# BOB-001.net
KiCad netlist of a schematic drawn in EAGLE
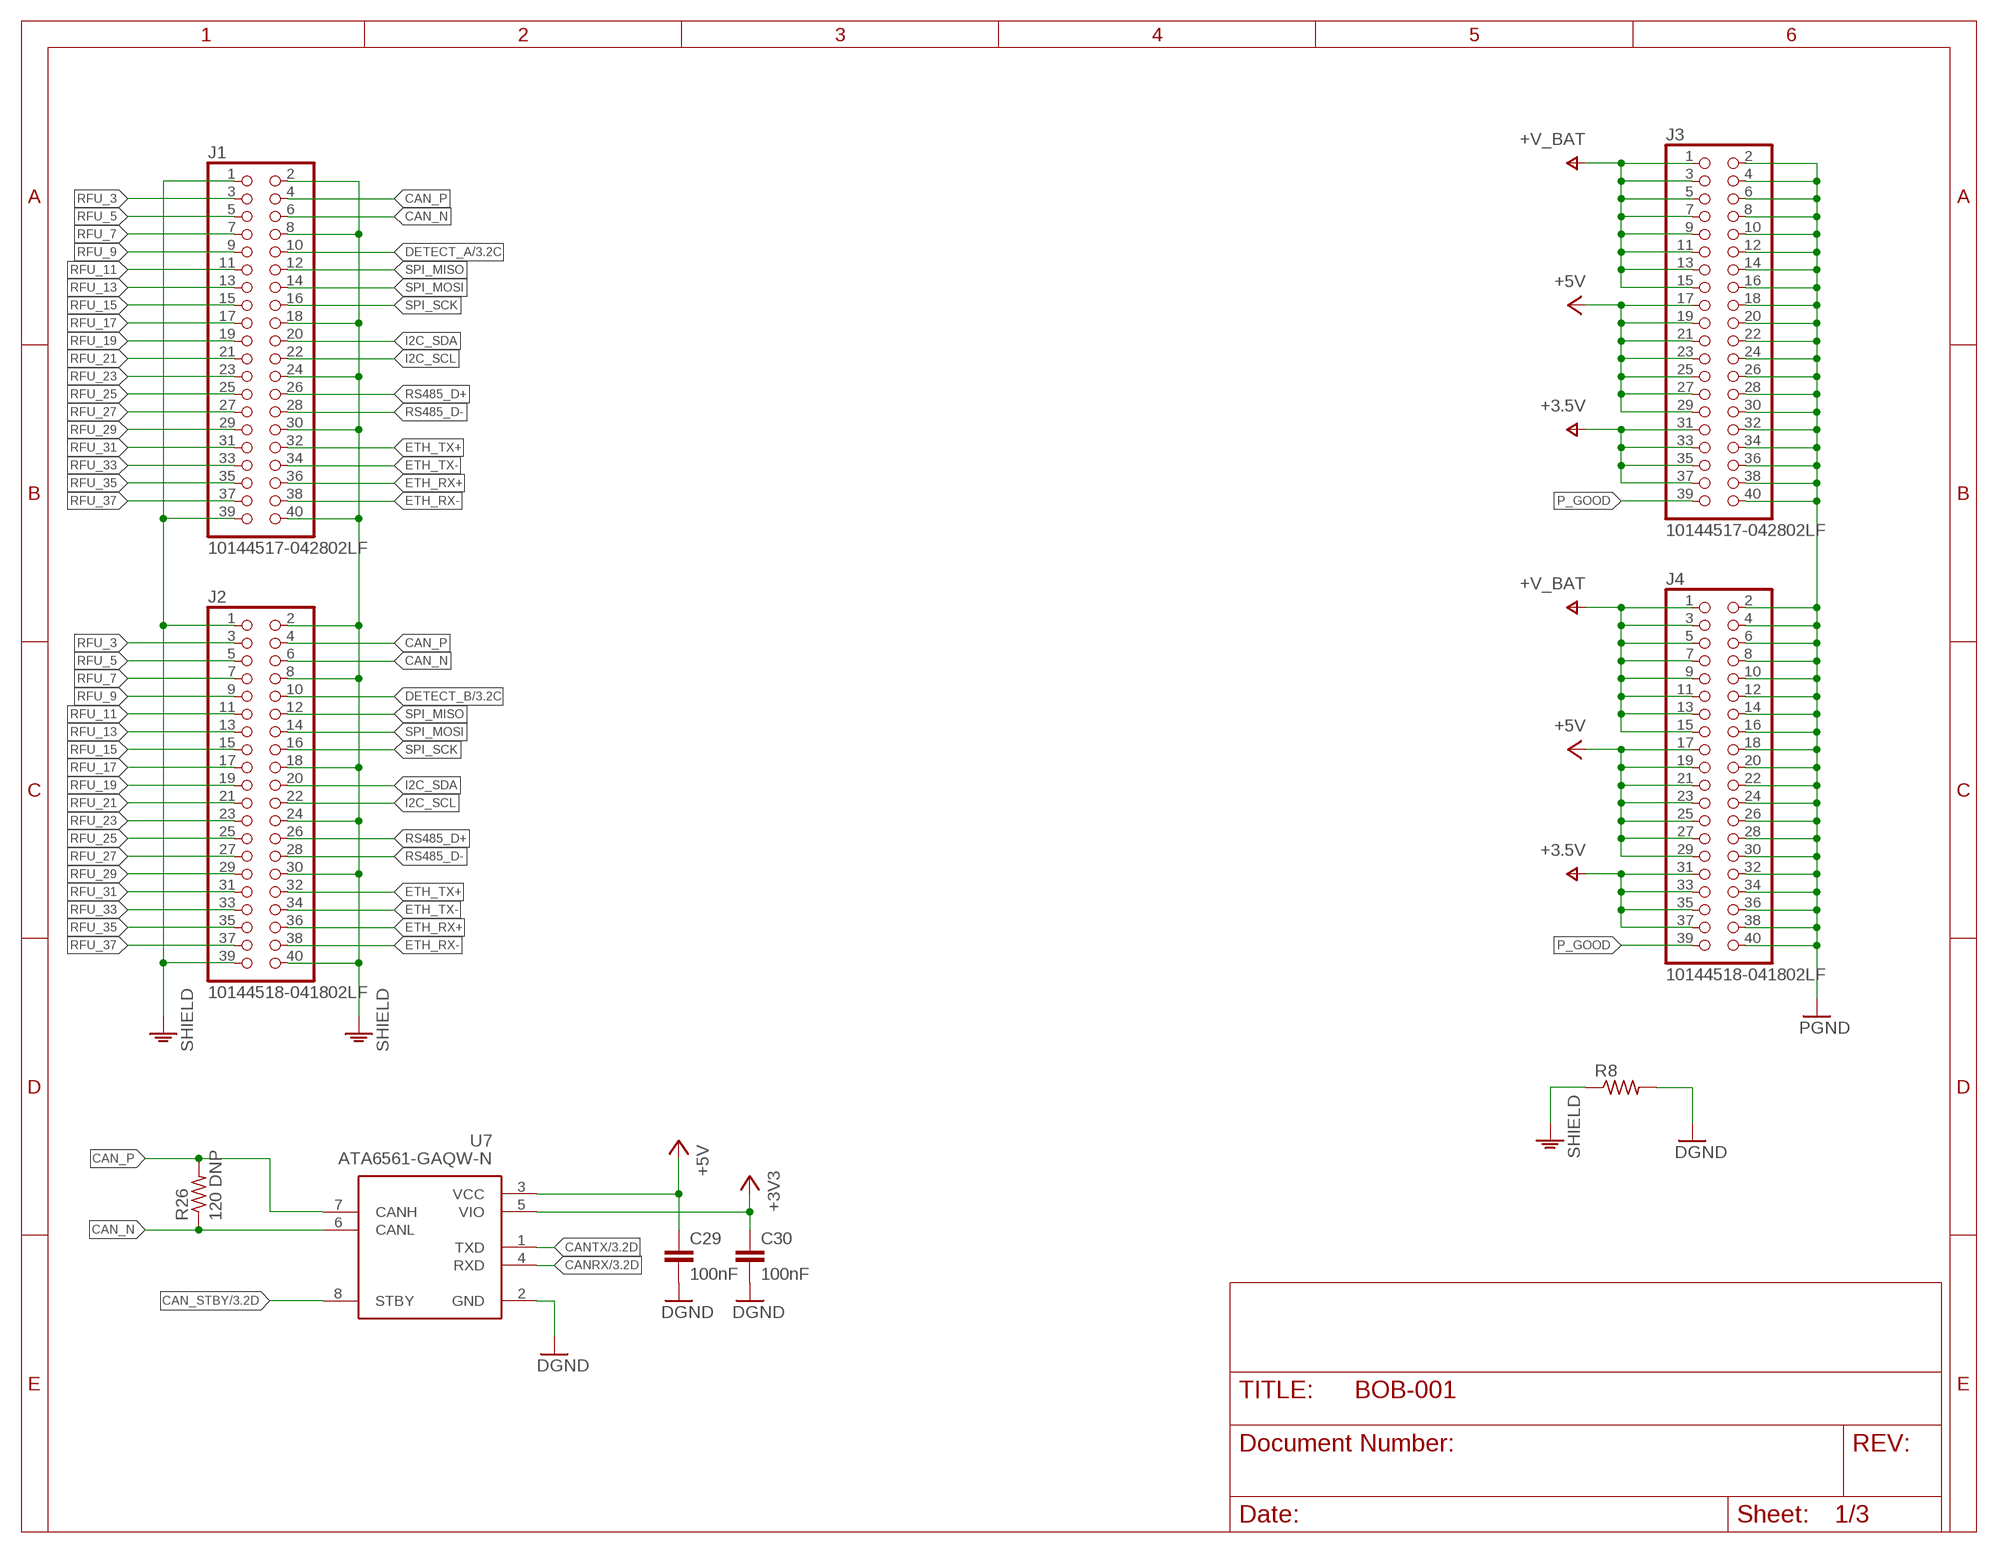
[diagram p0: schematic, sheet 1]
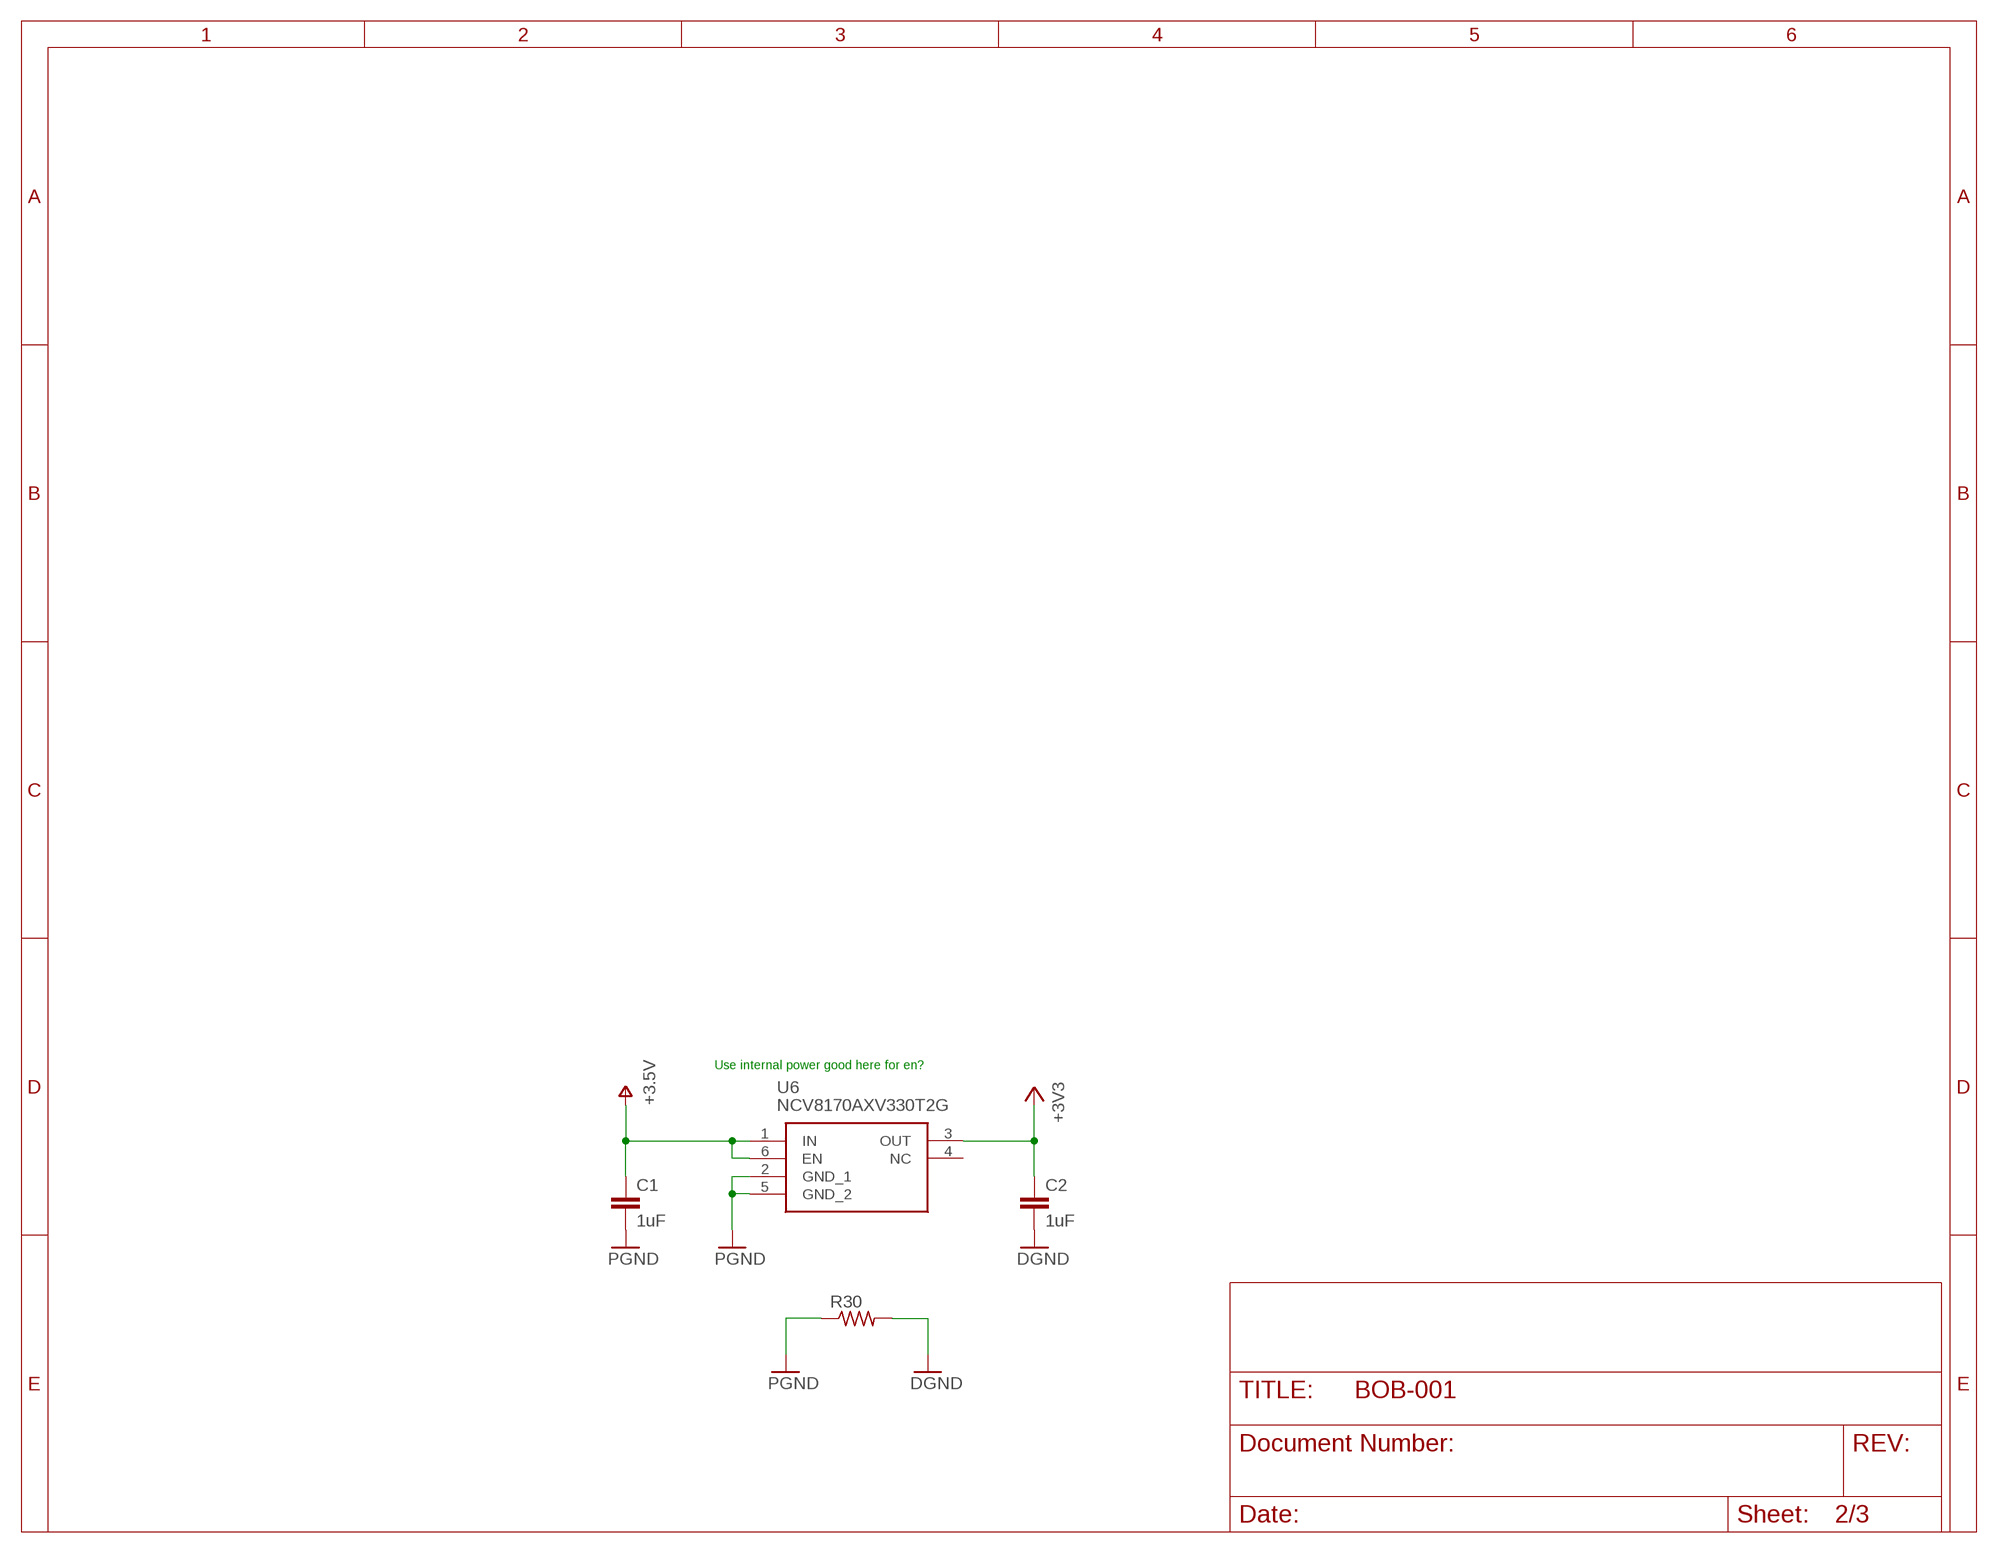
[diagram p1: schematic, sheet 2]
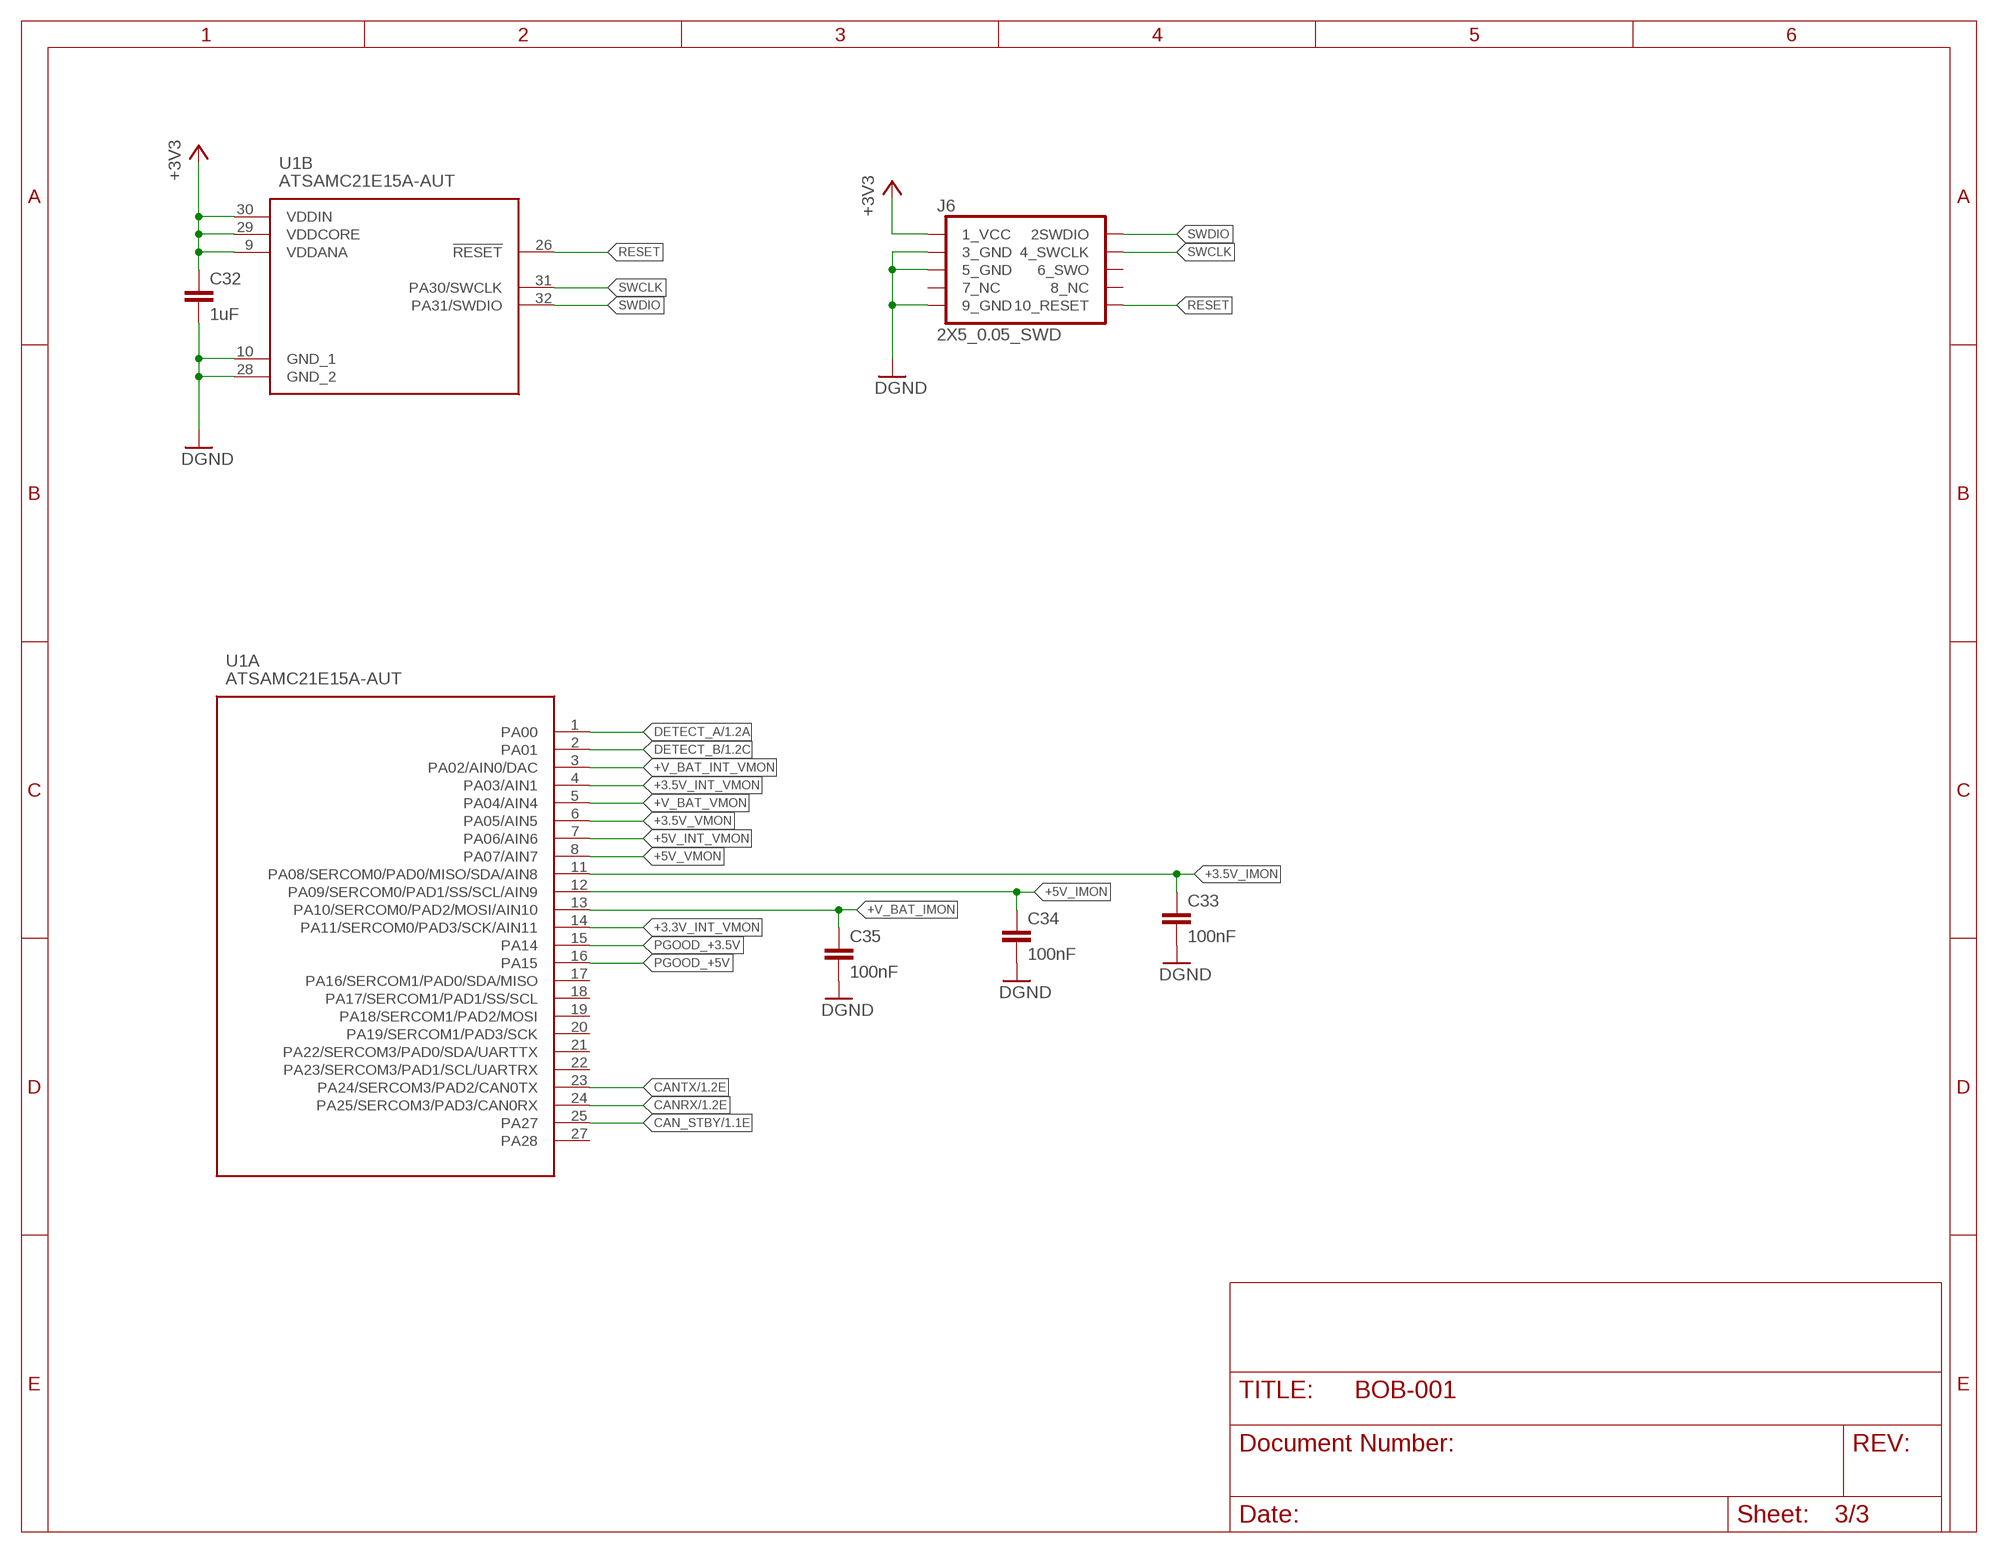
[diagram p2: schematic, sheet 3]

(export (version "E")
  (design (tool "Eeschema 10.0.6"))
  (components
    (comp (ref "C1")
      (value "1uF")
      (footprint "eagle-import:C0603")
      (libsource (lib "eagle-import") (part "C-EUC0603"))
    )
    (comp (ref "C2")
      (value "1uF")
      (footprint "eagle-import:C0603")
      (libsource (lib "eagle-import") (part "C-EUC0603"))
    )
    (comp (ref "R30")
      (value "R-US_R0402")
      (footprint "eagle-import:R0402")
      (libsource (lib "eagle-import") (part "R-US_R0402"))
    )
    (comp (ref "U6")
      (value "NCV8170AXV330T2G")
      (footprint "eagle-import:SOTFL50P160X60-6N")
      (fields (field (name "MOUSER_PART_NUMBER") "863-NCV8170AXV330T2G"))
      (libsource (lib "eagle-import") (part "NCV8170AXV330T2G"))
    )
    (comp (ref "C29")
      (value "100nF")
      (footprint "eagle-import:C0402")
      (libsource (lib "eagle-import") (part "C-EUC0402"))
    )
    (comp (ref "C30")
      (value "100nF")
      (footprint "eagle-import:C0402")
      (libsource (lib "eagle-import") (part "C-EUC0402"))
    )
    (comp (ref "J1")
      (value "10144517-042802LF")
      (footprint "eagle-import:10144517-042802LF")
      (libsource (lib "eagle-import") (part "10144517-042802LF"))
    )
    (comp (ref "J2")
      (value "10144518-041802LF")
      (footprint "eagle-import:10144518-041802LF")
      (libsource (lib "eagle-import") (part "10144518-041802LF"))
    )
    (comp (ref "J3")
      (value "10144517-042802LF")
      (footprint "eagle-import:10144517-042802LF")
      (libsource (lib "eagle-import") (part "10144517-042802LF"))
    )
    (comp (ref "J4")
      (value "10144518-041802LF")
      (footprint "eagle-import:10144518-041802LF")
      (libsource (lib "eagle-import") (part "10144518-041802LF"))
    )
    (comp (ref "R8")
      (value "R-US_R0402")
      (footprint "eagle-import:R0402")
      (libsource (lib "eagle-import") (part "R-US_R0402"))
    )
    (comp (ref "R26")
      (value "120 DNP")
      (footprint "eagle-import:R0402")
      (libsource (lib "eagle-import") (part "R-US_R0402"))
    )
    (comp (ref "U7")
      (value "ATA6561-GAQW-N")
      (footprint "eagle-import:SOIC127P600X175-8N")
      (fields (field (name "MOUSER_PART_NUMBER") "579-ATA6561-GAQW-N"))
      (libsource (lib "eagle-import") (part "ATA6561-GAQW-N"))
    )
    (comp (ref "C32")
      (value "1uF")
      (footprint "eagle-import:C0805")
      (libsource (lib "eagle-import") (part "C-EUC0805"))
    )
    (comp (ref "C33")
      (value "100nF")
      (footprint "eagle-import:C0402")
      (libsource (lib "eagle-import") (part "C-EUC0402"))
    )
    (comp (ref "C34")
      (value "100nF")
      (footprint "eagle-import:C0402")
      (libsource (lib "eagle-import") (part "C-EUC0402"))
    )
    (comp (ref "C35")
      (value "100nF")
      (footprint "eagle-import:C0402")
      (libsource (lib "eagle-import") (part "C-EUC0402"))
    )
    (comp (ref "J6")
      (value "2X5_0.05_SWD")
      (footprint "eagle-import:2X5_RIGHT")
      (libsource (lib "eagle-import") (part "2X5_0.05_SWD"))
    )
    (comp (ref "U1")
      (value "ATSAMC21E15A-AUT")
      (footprint "eagle-import:QFP80P900X900X120-32N")
      (libsource (lib "eagle-import") (part "ATSAMC21E15A-AUT"))
    )
  )
  (nets
    (net (code "1") (name "+3.3V_INT_VMON") (class "Default")
      (node (ref "U1") (pin "14") (pinfunction "PA11/SERCOM0/PAD3/SCK/AIN11_14") (pintype "bidirectional"))
    )
    (net (code "2") (name "+3.5V") (class "Default")
      (node (ref "C1") (pin "1") (pinfunction "1_1") (pintype "passive"))
      (node (ref "J3") (pin "31") (pinfunction "31_31") (pintype "passive"))
      (node (ref "J3") (pin "33") (pinfunction "33_33") (pintype "passive"))
      (node (ref "J3") (pin "35") (pinfunction "35_35") (pintype "passive"))
      (node (ref "J3") (pin "37") (pinfunction "37_37") (pintype "passive"))
      (node (ref "J4") (pin "31") (pinfunction "31_31") (pintype "passive"))
      (node (ref "J4") (pin "33") (pinfunction "33_33") (pintype "passive"))
      (node (ref "J4") (pin "35") (pinfunction "35_35") (pintype "passive"))
      (node (ref "J4") (pin "37") (pinfunction "37_37") (pintype "passive"))
      (node (ref "U6") (pin "1") (pinfunction "IN_1") (pintype "bidirectional"))
      (node (ref "U6") (pin "6") (pinfunction "EN_6") (pintype "bidirectional"))
    )
    (net (code "3") (name "+3.5V_IMON") (class "Default")
      (node (ref "C33") (pin "1") (pinfunction "1_1") (pintype "passive"))
      (node (ref "U1") (pin "11") (pinfunction "PA08/SERCOM0/PAD0/MISO/SDA/AIN8_11") (pintype "bidirectional"))
    )
    (net (code "4") (name "+3.5V_INT_VMON") (class "Default")
      (node (ref "U1") (pin "4") (pinfunction "PA03/AIN1_4") (pintype "bidirectional"))
    )
    (net (code "5") (name "+3.5V_VMON") (class "Default")
      (node (ref "U1") (pin "6") (pinfunction "PA05/AIN5_6") (pintype "bidirectional"))
    )
    (net (code "6") (name "+3V3") (class "Default")
      (node (ref "C2") (pin "1") (pinfunction "1_1") (pintype "passive"))
      (node (ref "C30") (pin "1") (pinfunction "1_1") (pintype "passive"))
      (node (ref "C32") (pin "1") (pinfunction "1_1") (pintype "passive"))
      (node (ref "J6") (pin "1") (pinfunction "1_VCC_1") (pintype "passive"))
      (node (ref "U1") (pin "29") (pinfunction "VDDCORE_29") (pintype "power_in"))
      (node (ref "U1") (pin "30") (pinfunction "VDDIN_30") (pintype "power_in"))
      (node (ref "U1") (pin "9") (pinfunction "VDDANA_9") (pintype "power_in"))
      (node (ref "U6") (pin "3") (pinfunction "OUT_3") (pintype "bidirectional"))
      (node (ref "U7") (pin "5") (pinfunction "VIO_5") (pintype "bidirectional"))
    )
    (net (code "7") (name "+5V") (class "Default")
      (node (ref "C29") (pin "1") (pinfunction "1_1") (pintype "passive"))
      (node (ref "J3") (pin "17") (pinfunction "17_17") (pintype "passive"))
      (node (ref "J3") (pin "19") (pinfunction "19_19") (pintype "passive"))
      (node (ref "J3") (pin "21") (pinfunction "21_21") (pintype "passive"))
      (node (ref "J3") (pin "23") (pinfunction "23_23") (pintype "passive"))
      (node (ref "J3") (pin "25") (pinfunction "25_25") (pintype "passive"))
      (node (ref "J3") (pin "27") (pinfunction "27_27") (pintype "passive"))
      (node (ref "J3") (pin "29") (pinfunction "29_29") (pintype "passive"))
      (node (ref "J4") (pin "17") (pinfunction "17_17") (pintype "passive"))
      (node (ref "J4") (pin "19") (pinfunction "19_19") (pintype "passive"))
      (node (ref "J4") (pin "21") (pinfunction "21_21") (pintype "passive"))
      (node (ref "J4") (pin "23") (pinfunction "23_23") (pintype "passive"))
      (node (ref "J4") (pin "25") (pinfunction "25_25") (pintype "passive"))
      (node (ref "J4") (pin "27") (pinfunction "27_27") (pintype "passive"))
      (node (ref "J4") (pin "29") (pinfunction "29_29") (pintype "passive"))
      (node (ref "U7") (pin "3") (pinfunction "VCC_3") (pintype "bidirectional"))
    )
    (net (code "8") (name "+5V_IMON") (class "Default")
      (node (ref "C34") (pin "1") (pinfunction "1_1") (pintype "passive"))
      (node (ref "U1") (pin "12") (pinfunction "PA09/SERCOM0/PAD1/SS/SCL/AIN9_12") (pintype "bidirectional"))
    )
    (net (code "9") (name "+5V_INT_VMON") (class "Default")
      (node (ref "U1") (pin "7") (pinfunction "PA06/AIN6_7") (pintype "bidirectional"))
    )
    (net (code "10") (name "+5V_VMON") (class "Default")
      (node (ref "U1") (pin "8") (pinfunction "PA07/AIN7_8") (pintype "bidirectional"))
    )
    (net (code "11") (name "+V_BAT") (class "Default")
      (node (ref "J3") (pin "1") (pinfunction "1_1") (pintype "passive"))
      (node (ref "J3") (pin "11") (pinfunction "11_11") (pintype "passive"))
      (node (ref "J3") (pin "13") (pinfunction "13_13") (pintype "passive"))
      (node (ref "J3") (pin "15") (pinfunction "15_15") (pintype "passive"))
      (node (ref "J3") (pin "3") (pinfunction "3_3") (pintype "passive"))
      (node (ref "J3") (pin "5") (pinfunction "5_5") (pintype "passive"))
      (node (ref "J3") (pin "7") (pinfunction "7_7") (pintype "passive"))
      (node (ref "J3") (pin "9") (pinfunction "9_9") (pintype "passive"))
      (node (ref "J4") (pin "1") (pinfunction "1_1") (pintype "passive"))
      (node (ref "J4") (pin "11") (pinfunction "11_11") (pintype "passive"))
      (node (ref "J4") (pin "13") (pinfunction "13_13") (pintype "passive"))
      (node (ref "J4") (pin "15") (pinfunction "15_15") (pintype "passive"))
      (node (ref "J4") (pin "3") (pinfunction "3_3") (pintype "passive"))
      (node (ref "J4") (pin "5") (pinfunction "5_5") (pintype "passive"))
      (node (ref "J4") (pin "7") (pinfunction "7_7") (pintype "passive"))
      (node (ref "J4") (pin "9") (pinfunction "9_9") (pintype "passive"))
    )
    (net (code "12") (name "+V_BAT_IMON") (class "Default")
      (node (ref "C35") (pin "1") (pinfunction "1_1") (pintype "passive"))
      (node (ref "U1") (pin "13") (pinfunction "PA10/SERCOM0/PAD2/MOSI/AIN10_13") (pintype "bidirectional"))
    )
    (net (code "13") (name "+V_BAT_INT_VMON") (class "Default")
      (node (ref "U1") (pin "3") (pinfunction "PA02/AIN0/DAC_3") (pintype "bidirectional"))
    )
    (net (code "14") (name "+V_BAT_VMON") (class "Default")
      (node (ref "U1") (pin "5") (pinfunction "PA04/AIN4_5") (pintype "bidirectional"))
    )
    (net (code "15") (name "CANRX") (class "Default")
      (node (ref "U1") (pin "24") (pinfunction "PA25/SERCOM3/PAD3/CAN0RX_24") (pintype "bidirectional"))
      (node (ref "U7") (pin "4") (pinfunction "RXD_4") (pintype "bidirectional"))
    )
    (net (code "16") (name "CANTX") (class "Default")
      (node (ref "U1") (pin "23") (pinfunction "PA24/SERCOM3/PAD2/CAN0TX_23") (pintype "bidirectional"))
      (node (ref "U7") (pin "1") (pinfunction "TXD_1") (pintype "bidirectional"))
    )
    (net (code "17") (name "CAN_N") (class "Default")
      (node (ref "J1") (pin "6") (pinfunction "6_6") (pintype "passive"))
      (node (ref "J2") (pin "6") (pinfunction "6_6") (pintype "passive"))
      (node (ref "R26") (pin "1") (pinfunction "1_1") (pintype "passive"))
      (node (ref "U7") (pin "6") (pinfunction "CANL_6") (pintype "bidirectional"))
    )
    (net (code "18") (name "CAN_P") (class "Default")
      (node (ref "J1") (pin "4") (pinfunction "4_4") (pintype "passive"))
      (node (ref "J2") (pin "4") (pinfunction "4_4") (pintype "passive"))
      (node (ref "R26") (pin "2") (pinfunction "2_2") (pintype "passive"))
      (node (ref "U7") (pin "7") (pinfunction "CANH_7") (pintype "bidirectional"))
    )
    (net (code "19") (name "CAN_STBY") (class "Default")
      (node (ref "U1") (pin "25") (pinfunction "PA27_25") (pintype "bidirectional"))
      (node (ref "U7") (pin "8") (pinfunction "STBY_8") (pintype "bidirectional"))
    )
    (net (code "20") (name "DETECT_A") (class "Default")
      (node (ref "J1") (pin "10") (pinfunction "10_10") (pintype "passive"))
      (node (ref "U1") (pin "1") (pinfunction "PA00_1") (pintype "bidirectional"))
    )
    (net (code "21") (name "DETECT_B") (class "Default")
      (node (ref "J2") (pin "10") (pinfunction "10_10") (pintype "passive"))
      (node (ref "U1") (pin "2") (pinfunction "PA01_2") (pintype "bidirectional"))
    )
    (net (code "22") (name "DGND") (class "Default")
      (node (ref "C2") (pin "2") (pinfunction "2_2") (pintype "passive"))
      (node (ref "C29") (pin "2") (pinfunction "2_2") (pintype "passive"))
      (node (ref "C30") (pin "2") (pinfunction "2_2") (pintype "passive"))
      (node (ref "C32") (pin "2") (pinfunction "2_2") (pintype "passive"))
      (node (ref "C33") (pin "2") (pinfunction "2_2") (pintype "passive"))
      (node (ref "C34") (pin "2") (pinfunction "2_2") (pintype "passive"))
      (node (ref "C35") (pin "2") (pinfunction "2_2") (pintype "passive"))
      (node (ref "J6") (pin "3") (pinfunction "3_GND_3") (pintype "passive"))
      (node (ref "J6") (pin "5") (pinfunction "5_GND_5") (pintype "passive"))
      (node (ref "J6") (pin "9") (pinfunction "9_GND_9") (pintype "passive"))
      (node (ref "R30") (pin "2") (pinfunction "2_2") (pintype "passive"))
      (node (ref "R8") (pin "2") (pinfunction "2_2") (pintype "passive"))
      (node (ref "U1") (pin "10") (pinfunction "GND_1_10") (pintype "power_in"))
      (node (ref "U1") (pin "28") (pinfunction "GND_2_28") (pintype "power_in"))
      (node (ref "U7") (pin "2") (pinfunction "GND_2") (pintype "bidirectional"))
    )
    (net (code "23") (name "ETH_RX+") (class "Default")
      (node (ref "J1") (pin "36") (pinfunction "36_36") (pintype "passive"))
      (node (ref "J2") (pin "36") (pinfunction "36_36") (pintype "passive"))
    )
    (net (code "24") (name "ETH_RX-") (class "Default")
      (node (ref "J1") (pin "38") (pinfunction "38_38") (pintype "passive"))
      (node (ref "J2") (pin "38") (pinfunction "38_38") (pintype "passive"))
    )
    (net (code "25") (name "ETH_TX+") (class "Default")
      (node (ref "J1") (pin "32") (pinfunction "32_32") (pintype "passive"))
      (node (ref "J2") (pin "32") (pinfunction "32_32") (pintype "passive"))
    )
    (net (code "26") (name "ETH_TX-") (class "Default")
      (node (ref "J1") (pin "34") (pinfunction "34_34") (pintype "passive"))
      (node (ref "J2") (pin "34") (pinfunction "34_34") (pintype "passive"))
    )
    (net (code "27") (name "I2C_SCL") (class "Default")
      (node (ref "J1") (pin "22") (pinfunction "22_22") (pintype "passive"))
      (node (ref "J2") (pin "22") (pinfunction "22_22") (pintype "passive"))
    )
    (net (code "28") (name "I2C_SDA") (class "Default")
      (node (ref "J1") (pin "20") (pinfunction "20_20") (pintype "passive"))
      (node (ref "J2") (pin "20") (pinfunction "20_20") (pintype "passive"))
    )
    (net (code "29") (name "PGND") (class "Default")
      (node (ref "C1") (pin "2") (pinfunction "2_2") (pintype "passive"))
      (node (ref "J3") (pin "10") (pinfunction "10_10") (pintype "passive"))
      (node (ref "J3") (pin "12") (pinfunction "12_12") (pintype "passive"))
      (node (ref "J3") (pin "14") (pinfunction "14_14") (pintype "passive"))
      (node (ref "J3") (pin "16") (pinfunction "16_16") (pintype "passive"))
      (node (ref "J3") (pin "18") (pinfunction "18_18") (pintype "passive"))
      (node (ref "J3") (pin "2") (pinfunction "2_2") (pintype "passive"))
      (node (ref "J3") (pin "20") (pinfunction "20_20") (pintype "passive"))
      (node (ref "J3") (pin "22") (pinfunction "22_22") (pintype "passive"))
      (node (ref "J3") (pin "24") (pinfunction "24_24") (pintype "passive"))
      (node (ref "J3") (pin "26") (pinfunction "26_26") (pintype "passive"))
      (node (ref "J3") (pin "28") (pinfunction "28_28") (pintype "passive"))
      (node (ref "J3") (pin "30") (pinfunction "30_30") (pintype "passive"))
      (node (ref "J3") (pin "32") (pinfunction "32_32") (pintype "passive"))
      (node (ref "J3") (pin "34") (pinfunction "34_34") (pintype "passive"))
      (node (ref "J3") (pin "36") (pinfunction "36_36") (pintype "passive"))
      (node (ref "J3") (pin "38") (pinfunction "38_38") (pintype "passive"))
      (node (ref "J3") (pin "4") (pinfunction "4_4") (pintype "passive"))
      (node (ref "J3") (pin "40") (pinfunction "40_40") (pintype "passive"))
      (node (ref "J3") (pin "6") (pinfunction "6_6") (pintype "passive"))
      (node (ref "J3") (pin "8") (pinfunction "8_8") (pintype "passive"))
      (node (ref "J4") (pin "10") (pinfunction "10_10") (pintype "passive"))
      (node (ref "J4") (pin "12") (pinfunction "12_12") (pintype "passive"))
      (node (ref "J4") (pin "14") (pinfunction "14_14") (pintype "passive"))
      (node (ref "J4") (pin "16") (pinfunction "16_16") (pintype "passive"))
      (node (ref "J4") (pin "18") (pinfunction "18_18") (pintype "passive"))
      (node (ref "J4") (pin "2") (pinfunction "2_2") (pintype "passive"))
      (node (ref "J4") (pin "20") (pinfunction "20_20") (pintype "passive"))
      (node (ref "J4") (pin "22") (pinfunction "22_22") (pintype "passive"))
      (node (ref "J4") (pin "24") (pinfunction "24_24") (pintype "passive"))
      (node (ref "J4") (pin "26") (pinfunction "26_26") (pintype "passive"))
      (node (ref "J4") (pin "28") (pinfunction "28_28") (pintype "passive"))
      (node (ref "J4") (pin "30") (pinfunction "30_30") (pintype "passive"))
      (node (ref "J4") (pin "32") (pinfunction "32_32") (pintype "passive"))
      (node (ref "J4") (pin "34") (pinfunction "34_34") (pintype "passive"))
      (node (ref "J4") (pin "36") (pinfunction "36_36") (pintype "passive"))
      (node (ref "J4") (pin "38") (pinfunction "38_38") (pintype "passive"))
      (node (ref "J4") (pin "4") (pinfunction "4_4") (pintype "passive"))
      (node (ref "J4") (pin "40") (pinfunction "40_40") (pintype "passive"))
      (node (ref "J4") (pin "6") (pinfunction "6_6") (pintype "passive"))
      (node (ref "J4") (pin "8") (pinfunction "8_8") (pintype "passive"))
      (node (ref "R30") (pin "1") (pinfunction "1_1") (pintype "passive"))
      (node (ref "U6") (pin "2") (pinfunction "GND_1_2") (pintype "bidirectional"))
      (node (ref "U6") (pin "5") (pinfunction "GND_2_5") (pintype "bidirectional"))
    )
    (net (code "30") (name "PGOOD_+3.5V") (class "Default")
      (node (ref "U1") (pin "15") (pinfunction "PA14_15") (pintype "bidirectional"))
    )
    (net (code "31") (name "PGOOD_+5V") (class "Default")
      (node (ref "U1") (pin "16") (pinfunction "PA15_16") (pintype "bidirectional"))
    )
    (net (code "32") (name "P_GOOD") (class "Default")
      (node (ref "J3") (pin "39") (pinfunction "39_39") (pintype "passive"))
      (node (ref "J4") (pin "39") (pinfunction "39_39") (pintype "passive"))
    )
    (net (code "33") (name "RESET") (class "Default")
      (node (ref "J6") (pin "10") (pinfunction "10_RESET_10") (pintype "passive"))
      (node (ref "U1") (pin "26") (pinfunction "~{RESET}_26") (pintype "input"))
    )
    (net (code "34") (name "RFU_3") (class "Default")
      (node (ref "J1") (pin "3") (pinfunction "3_3") (pintype "passive"))
      (node (ref "J2") (pin "3") (pinfunction "3_3") (pintype "passive"))
    )
    (net (code "35") (name "RFU_5") (class "Default")
      (node (ref "J1") (pin "5") (pinfunction "5_5") (pintype "passive"))
      (node (ref "J2") (pin "5") (pinfunction "5_5") (pintype "passive"))
    )
    (net (code "36") (name "RFU_7") (class "Default")
      (node (ref "J1") (pin "7") (pinfunction "7_7") (pintype "passive"))
      (node (ref "J2") (pin "7") (pinfunction "7_7") (pintype "passive"))
    )
    (net (code "37") (name "RFU_9") (class "Default")
      (node (ref "J1") (pin "9") (pinfunction "9_9") (pintype "passive"))
      (node (ref "J2") (pin "9") (pinfunction "9_9") (pintype "passive"))
    )
    (net (code "38") (name "RFU_11") (class "Default")
      (node (ref "J1") (pin "11") (pinfunction "11_11") (pintype "passive"))
      (node (ref "J2") (pin "11") (pinfunction "11_11") (pintype "passive"))
    )
    (net (code "39") (name "RFU_13") (class "Default")
      (node (ref "J1") (pin "13") (pinfunction "13_13") (pintype "passive"))
      (node (ref "J2") (pin "13") (pinfunction "13_13") (pintype "passive"))
    )
    (net (code "40") (name "RFU_15") (class "Default")
      (node (ref "J1") (pin "15") (pinfunction "15_15") (pintype "passive"))
      (node (ref "J2") (pin "15") (pinfunction "15_15") (pintype "passive"))
    )
    (net (code "41") (name "RFU_17") (class "Default")
      (node (ref "J1") (pin "17") (pinfunction "17_17") (pintype "passive"))
      (node (ref "J2") (pin "17") (pinfunction "17_17") (pintype "passive"))
    )
    (net (code "42") (name "RFU_19") (class "Default")
      (node (ref "J1") (pin "19") (pinfunction "19_19") (pintype "passive"))
      (node (ref "J2") (pin "19") (pinfunction "19_19") (pintype "passive"))
    )
    (net (code "43") (name "RFU_21") (class "Default")
      (node (ref "J1") (pin "21") (pinfunction "21_21") (pintype "passive"))
      (node (ref "J2") (pin "21") (pinfunction "21_21") (pintype "passive"))
    )
    (net (code "44") (name "RFU_23") (class "Default")
      (node (ref "J1") (pin "23") (pinfunction "23_23") (pintype "passive"))
      (node (ref "J2") (pin "23") (pinfunction "23_23") (pintype "passive"))
    )
    (net (code "45") (name "RFU_25") (class "Default")
      (node (ref "J1") (pin "25") (pinfunction "25_25") (pintype "passive"))
      (node (ref "J2") (pin "25") (pinfunction "25_25") (pintype "passive"))
    )
    (net (code "46") (name "RFU_27") (class "Default")
      (node (ref "J1") (pin "27") (pinfunction "27_27") (pintype "passive"))
      (node (ref "J2") (pin "27") (pinfunction "27_27") (pintype "passive"))
    )
    (net (code "47") (name "RFU_29") (class "Default")
      (node (ref "J1") (pin "29") (pinfunction "29_29") (pintype "passive"))
      (node (ref "J2") (pin "29") (pinfunction "29_29") (pintype "passive"))
    )
    (net (code "48") (name "RFU_31") (class "Default")
      (node (ref "J1") (pin "31") (pinfunction "31_31") (pintype "passive"))
      (node (ref "J2") (pin "31") (pinfunction "31_31") (pintype "passive"))
    )
    (net (code "49") (name "RFU_33") (class "Default")
      (node (ref "J1") (pin "33") (pinfunction "33_33") (pintype "passive"))
      (node (ref "J2") (pin "33") (pinfunction "33_33") (pintype "passive"))
    )
    (net (code "50") (name "RFU_35") (class "Default")
      (node (ref "J1") (pin "35") (pinfunction "35_35") (pintype "passive"))
      (node (ref "J2") (pin "35") (pinfunction "35_35") (pintype "passive"))
    )
    (net (code "51") (name "RFU_37") (class "Default")
      (node (ref "J1") (pin "37") (pinfunction "37_37") (pintype "passive"))
      (node (ref "J2") (pin "37") (pinfunction "37_37") (pintype "passive"))
    )
    (net (code "52") (name "RS485_D+") (class "Default")
      (node (ref "J1") (pin "26") (pinfunction "26_26") (pintype "passive"))
      (node (ref "J2") (pin "26") (pinfunction "26_26") (pintype "passive"))
    )
    (net (code "53") (name "RS485_D-") (class "Default")
      (node (ref "J1") (pin "28") (pinfunction "28_28") (pintype "passive"))
      (node (ref "J2") (pin "28") (pinfunction "28_28") (pintype "passive"))
    )
    (net (code "54") (name "SHIELD") (class "Default")
      (node (ref "J1") (pin "1") (pinfunction "1_1") (pintype "passive"))
      (node (ref "J1") (pin "18") (pinfunction "18_18") (pintype "passive"))
      (node (ref "J1") (pin "2") (pinfunction "2_2") (pintype "passive"))
      (node (ref "J1") (pin "24") (pinfunction "24_24") (pintype "passive"))
      (node (ref "J1") (pin "30") (pinfunction "30_30") (pintype "passive"))
      (node (ref "J1") (pin "39") (pinfunction "39_39") (pintype "passive"))
      (node (ref "J1") (pin "40") (pinfunction "40_40") (pintype "passive"))
      (node (ref "J1") (pin "8") (pinfunction "8_8") (pintype "passive"))
      (node (ref "J2") (pin "1") (pinfunction "1_1") (pintype "passive"))
      (node (ref "J2") (pin "18") (pinfunction "18_18") (pintype "passive"))
      (node (ref "J2") (pin "2") (pinfunction "2_2") (pintype "passive"))
      (node (ref "J2") (pin "24") (pinfunction "24_24") (pintype "passive"))
      (node (ref "J2") (pin "30") (pinfunction "30_30") (pintype "passive"))
      (node (ref "J2") (pin "39") (pinfunction "39_39") (pintype "passive"))
      (node (ref "J2") (pin "40") (pinfunction "40_40") (pintype "passive"))
      (node (ref "J2") (pin "8") (pinfunction "8_8") (pintype "passive"))
      (node (ref "R8") (pin "1") (pinfunction "1_1") (pintype "passive"))
    )
    (net (code "55") (name "SPI_MISO") (class "Default")
      (node (ref "J1") (pin "12") (pinfunction "12_12") (pintype "passive"))
      (node (ref "J2") (pin "12") (pinfunction "12_12") (pintype "passive"))
    )
    (net (code "56") (name "SPI_MOSI") (class "Default")
      (node (ref "J1") (pin "14") (pinfunction "14_14") (pintype "passive"))
      (node (ref "J2") (pin "14") (pinfunction "14_14") (pintype "passive"))
    )
    (net (code "57") (name "SPI_SCK") (class "Default")
      (node (ref "J1") (pin "16") (pinfunction "16_16") (pintype "passive"))
      (node (ref "J2") (pin "16") (pinfunction "16_16") (pintype "passive"))
    )
    (net (code "58") (name "SWCLK") (class "Default")
      (node (ref "J6") (pin "4") (pinfunction "4_SWCLK_4") (pintype "passive"))
      (node (ref "U1") (pin "31") (pinfunction "PA30/SWCLK_31") (pintype "bidirectional"))
    )
    (net (code "59") (name "SWDIO") (class "Default")
      (node (ref "J6") (pin "2") (pinfunction "2SWDIO_2") (pintype "passive"))
      (node (ref "U1") (pin "32") (pinfunction "PA31/SWDIO_32") (pintype "bidirectional"))
    )
    (net (code "60") (name "unconnected-(J6-6_SWO-Pad6)") (class "Default")
      (node (ref "J6") (pin "6") (pinfunction "6_SWO_6") (pintype "passive"))
    )
    (net (code "61") (name "unconnected-(J6-7_NC-Pad7)") (class "Default")
      (node (ref "J6") (pin "7") (pinfunction "7_NC_7") (pintype "passive"))
    )
    (net (code "62") (name "unconnected-(J6-8_NC-Pad8)") (class "Default")
      (node (ref "J6") (pin "8") (pinfunction "8_NC_8") (pintype "passive"))
    )
    (net (code "63") (name "unconnected-(U1A-PA16{slash}SERCOM1{slash}PAD0{slash}SDA{slash}MISO-Pad17)") (class "Default")
      (node (ref "U1") (pin "17") (pinfunction "PA16/SERCOM1/PAD0/SDA/MISO_17") (pintype "bidirectional"))
    )
    (net (code "64") (name "unconnected-(U1A-PA17{slash}SERCOM1{slash}PAD1{slash}SS{slash}SCL-Pad18)") (class "Default")
      (node (ref "U1") (pin "18") (pinfunction "PA17/SERCOM1/PAD1/SS/SCL_18") (pintype "bidirectional"))
    )
    (net (code "65") (name "unconnected-(U1A-PA18{slash}SERCOM1{slash}PAD2{slash}MOSI-Pad19)") (class "Default")
      (node (ref "U1") (pin "19") (pinfunction "PA18/SERCOM1/PAD2/MOSI_19") (pintype "bidirectional"))
    )
    (net (code "66") (name "unconnected-(U1A-PA19{slash}SERCOM1{slash}PAD3{slash}SCK-Pad20)") (class "Default")
      (node (ref "U1") (pin "20") (pinfunction "PA19/SERCOM1/PAD3/SCK_20") (pintype "bidirectional"))
    )
    (net (code "67") (name "unconnected-(U1A-PA22{slash}SERCOM3{slash}PAD0{slash}SDA{slash}UARTTX-Pad21)") (class "Default")
      (node (ref "U1") (pin "21") (pinfunction "PA22/SERCOM3/PAD0/SDA/UARTTX_21") (pintype "bidirectional"))
    )
    (net (code "68") (name "unconnected-(U1A-PA23{slash}SERCOM3{slash}PAD1{slash}SCL{slash}UARTRX-Pad22)") (class "Default")
      (node (ref "U1") (pin "22") (pinfunction "PA23/SERCOM3/PAD1/SCL/UARTRX_22") (pintype "bidirectional"))
    )
    (net (code "69") (name "unconnected-(U1A-PA28-Pad27)") (class "Default")
      (node (ref "U1") (pin "27") (pinfunction "PA28_27") (pintype "bidirectional"))
    )
    (net (code "70") (name "unconnected-(U6-NC-Pad4)") (class "Default")
      (node (ref "U6") (pin "4") (pinfunction "NC_4") (pintype "no_connect"))
    )
  )
)
